# Switched_Outlet_Rev_C.net
KiCad netlist of a schematic drawn in EAGLE
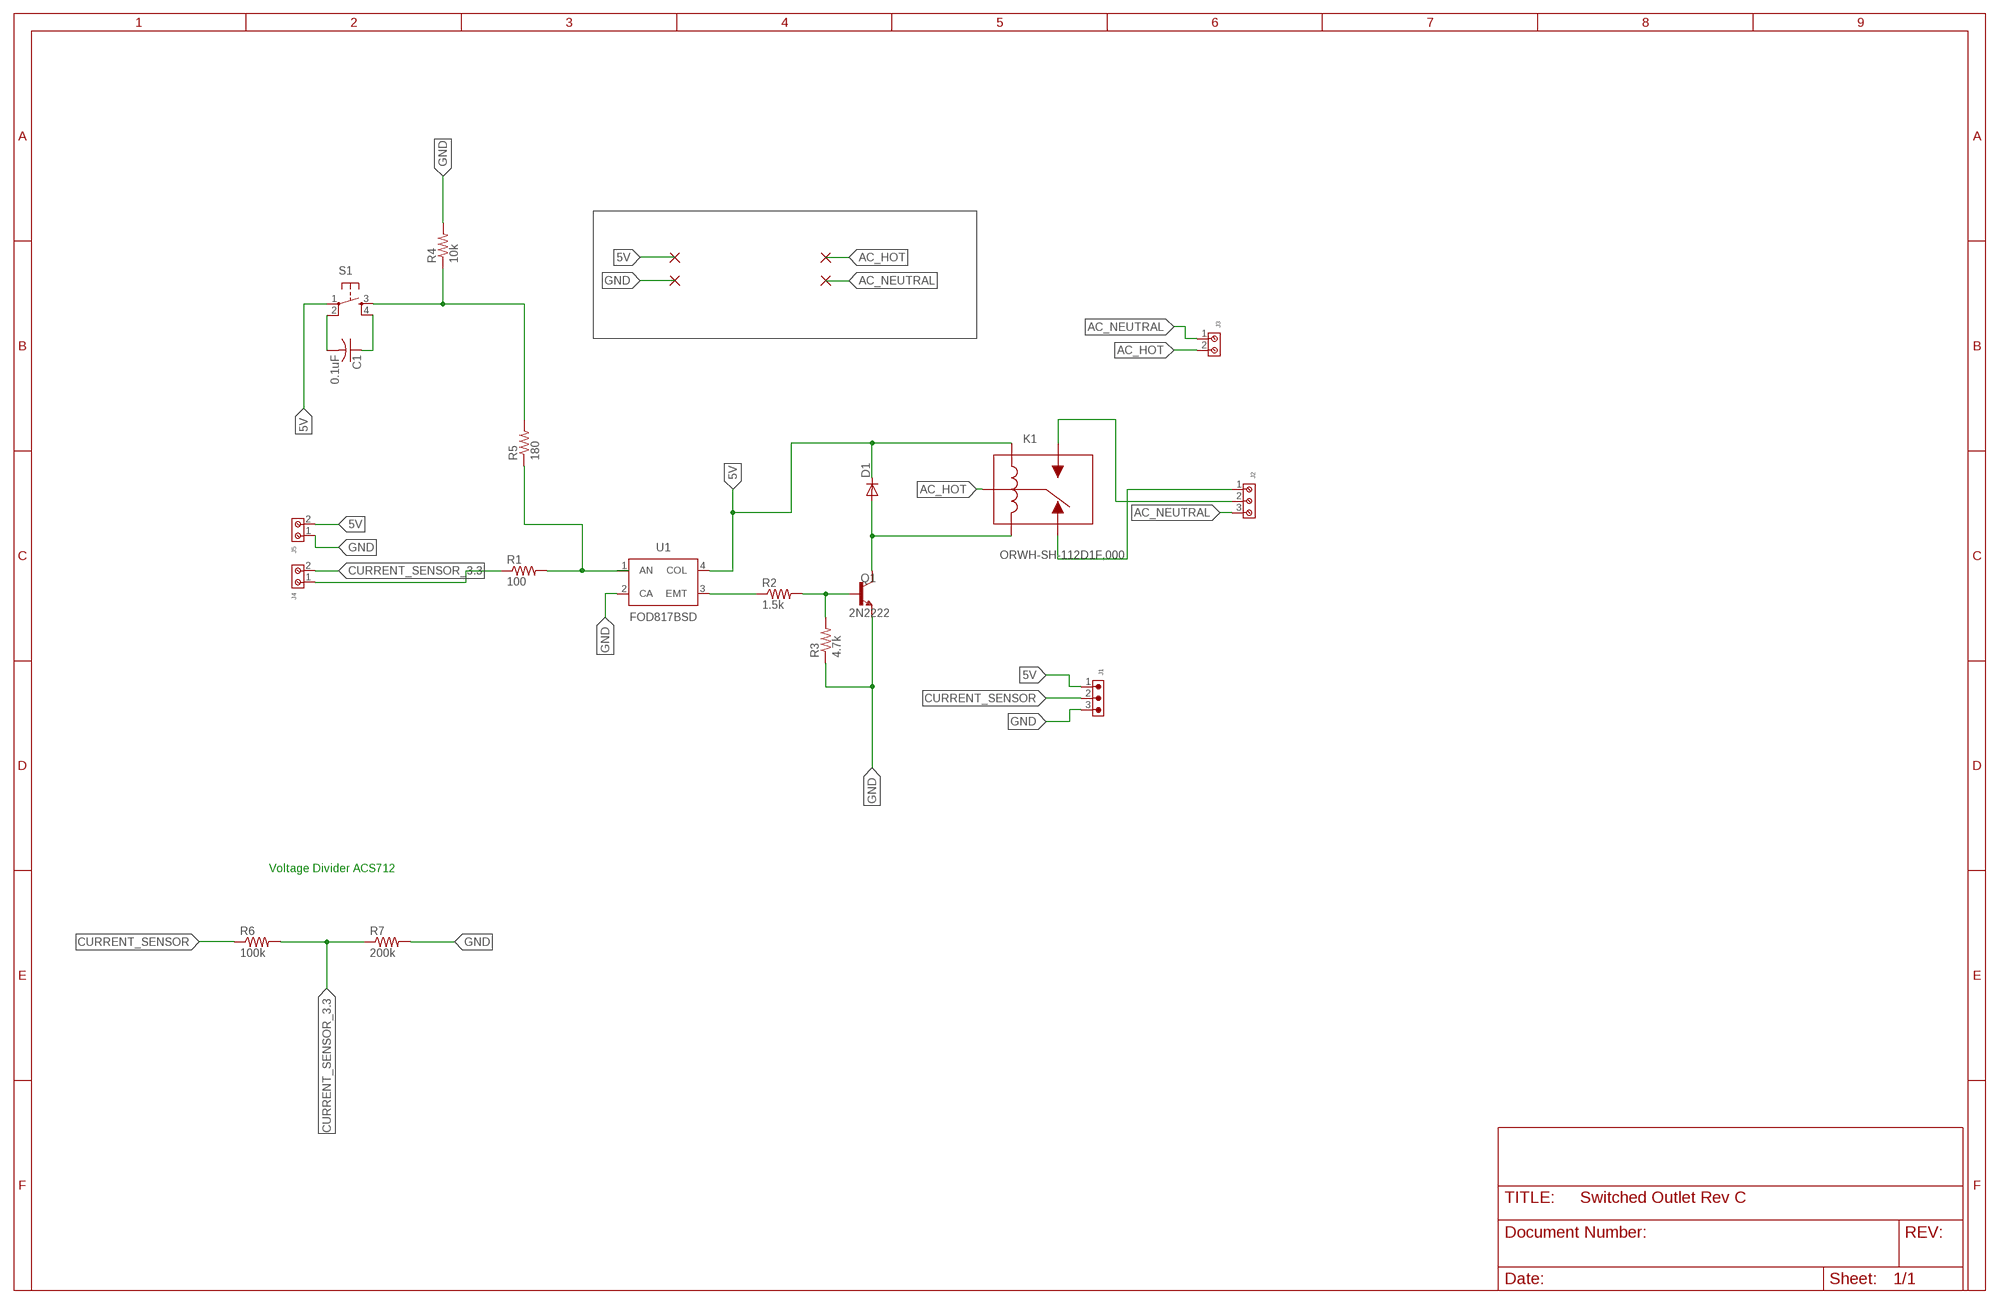
[diagram p0: schematic, sheet 1]

(export (version "E")
  (design (tool "Eeschema 10.0.6"))
  (components
    (comp (ref "C1")
      (value "0.1uF")
      (footprint "eagle-import:C050-024X044")
      (libsource (lib "eagle-import") (part "CAPACITOR-CERAMIC"))
    )
    (comp (ref "D1")
      (value "1N4000")
      (footprint "eagle-import:DO41-10")
      (libsource (lib "eagle-import") (part "1N4000"))
    )
    (comp (ref "J1")
      (value "6130XX11121_61300311121")
      (footprint "eagle-import:61300311121")
      (libsource (lib "eagle-import") (part "6130XX11121_61300311121"))
    )
    (comp (ref "J2")
      (value "691102710003")
      (footprint "eagle-import:691102710003")
      (libsource (lib "eagle-import") (part "691102710003"))
    )
    (comp (ref "J3")
      (value "691102710002")
      (footprint "eagle-import:691102710002")
      (libsource (lib "eagle-import") (part "691102710002"))
    )
    (comp (ref "J4")
      (value "691103110002")
      (footprint "eagle-import:691103110002")
      (libsource (lib "eagle-import") (part "691103110002"))
    )
    (comp (ref "J5")
      (value "691103110002")
      (footprint "eagle-import:691103110002")
      (libsource (lib "eagle-import") (part "691103110002"))
    )
    (comp (ref "K1")
      (value "ORWH-SH-112D1F,000")
      (footprint "eagle-import:ORWH-SH-112D1F,000")
      (fields
        (field (name "DIGIKEY_PART_NUMBER") "PB2029-ND")
        (field (name "MANUFACTURER") "TE Connectivity Potter & Brumfield Relays")
        (field (name "CREATED_BY") "PCBLayout.com")
      )
      (libsource (lib "eagle-import") (part "ORWH-SH-112D1F,000"))
    )
    (comp (ref "Q1")
      (value "2N2222")
      (footprint "eagle-import:TO92-EBC-OVAL")
      (libsource (lib "eagle-import") (part "2N2222"))
    )
    (comp (ref "R1")
      (value "100")
      (footprint "eagle-import:0207_10")
      (libsource (lib "eagle-import") (part "RESISTOR"))
    )
    (comp (ref "R2")
      (value "1.5k")
      (footprint "eagle-import:0207_10")
      (libsource (lib "eagle-import") (part "RESISTOR"))
    )
    (comp (ref "R3")
      (value "4.7k")
      (footprint "eagle-import:0207_10")
      (libsource (lib "eagle-import") (part "RESISTOR"))
    )
    (comp (ref "R4")
      (value "10k")
      (footprint "eagle-import:0207_10")
      (libsource (lib "eagle-import") (part "RESISTOR"))
    )
    (comp (ref "R5")
      (value "180")
      (footprint "eagle-import:0207_10")
      (libsource (lib "eagle-import") (part "RESISTOR"))
    )
    (comp (ref "R6")
      (value "100k")
      (footprint "eagle-import:0207_10")
      (libsource (lib "eagle-import") (part "RESISTOR"))
    )
    (comp (ref "R7")
      (value "200k")
      (footprint "eagle-import:0207_10")
      (libsource (lib "eagle-import") (part "RESISTOR"))
    )
    (comp (ref "S1")
      (value "TACTILE-BUTTON10XX")
      (footprint "eagle-import:B3F-10XX")
      (libsource (lib "eagle-import") (part "TACTILE-BUTTON10XX"))
    )
    (comp (ref "U1")
      (value "FOD817BSD")
      (footprint "eagle-import:DIP1016W60P279L460H460Q4B")
      (fields (field (name "MANUFACTURER") "ON Semiconductor"))
      (libsource (lib "eagle-import") (part "FOD817BSDSMT"))
    )
  )
  (nets
    (net (code "1") (name "5V") (class "Default")
      (node (ref "D1") (pin "C") (pinfunction "C_C") (pintype "passive"))
      (node (ref "J1") (pin "1") (pinfunction "1_1") (pintype "passive"))
      (node (ref "J5") (pin "2") (pinfunction "2_2") (pintype "passive"))
      (node (ref "K1") (pin "1") (pinfunction "1_1") (pintype "passive"))
      (node (ref "S1") (pin "1") (pinfunction "P_1") (pintype "passive"))
      (node (ref "U1") (pin "4") (pinfunction "COL_4") (pintype "input"))
    )
    (net (code "2") (name "AC_HOT") (class "Default")
      (node (ref "J3") (pin "2") (pinfunction "2_2") (pintype "passive"))
      (node (ref "K1") (pin "2") (pinfunction "2_2") (pintype "passive"))
    )
    (net (code "3") (name "AC_NEUTRAL") (class "Default")
      (node (ref "J2") (pin "3") (pinfunction "3_3") (pintype "passive"))
      (node (ref "J3") (pin "1") (pinfunction "1_1") (pintype "passive"))
    )
    (net (code "4") (name "CURRENT_SENSOR") (class "Default")
      (node (ref "J1") (pin "2") (pinfunction "2_2") (pintype "passive"))
      (node (ref "R6") (pin "1") (pinfunction "1_1") (pintype "passive"))
    )
    (net (code "5") (name "CURRENT_SENSOR_3.3") (class "Default")
      (node (ref "J4") (pin "2") (pinfunction "2_2") (pintype "passive"))
      (node (ref "R6") (pin "2") (pinfunction "2_2") (pintype "passive"))
      (node (ref "R7") (pin "1") (pinfunction "1_1") (pintype "passive"))
    )
    (net (code "6") (name "GND") (class "Default")
      (node (ref "J1") (pin "3") (pinfunction "3_3") (pintype "passive"))
      (node (ref "J5") (pin "1") (pinfunction "1_1") (pintype "passive"))
      (node (ref "Q1") (pin "E") (pinfunction "E_E") (pintype "passive"))
      (node (ref "R3") (pin "1") (pinfunction "1_1") (pintype "passive"))
      (node (ref "R4") (pin "2") (pinfunction "2_2") (pintype "passive"))
      (node (ref "R7") (pin "2") (pinfunction "2_2") (pintype "passive"))
      (node (ref "U1") (pin "2") (pinfunction "CA_2") (pintype "bidirectional"))
    )
    (net (code "7") (name "Net-(D1-PadA)") (class "Default")
      (node (ref "D1") (pin "A") (pinfunction "A_A") (pintype "passive"))
      (node (ref "K1") (pin "3") (pinfunction "3_3") (pintype "passive"))
      (node (ref "Q1") (pin "C") (pinfunction "C_C") (pintype "passive"))
    )
    (net (code "8") (name "Net-(J2-Pad1)") (class "Default")
      (node (ref "J2") (pin "1") (pinfunction "1_1") (pintype "passive"))
      (node (ref "K1") (pin "4") (pinfunction "4_4") (pintype "passive"))
    )
    (net (code "9") (name "Net-(J2-Pad2)") (class "Default")
      (node (ref "J2") (pin "2") (pinfunction "2_2") (pintype "passive"))
      (node (ref "K1") (pin "5") (pinfunction "5_5") (pintype "passive"))
    )
    (net (code "10") (name "Net-(J4-Pad1)") (class "Default")
      (node (ref "J4") (pin "1") (pinfunction "1_1") (pintype "passive"))
      (node (ref "R1") (pin "1") (pinfunction "1_1") (pintype "passive"))
    )
    (net (code "11") (name "Net-(Q1-PadB)") (class "Default")
      (node (ref "Q1") (pin "B") (pinfunction "B_B") (pintype "passive"))
      (node (ref "R2") (pin "2") (pinfunction "2_2") (pintype "passive"))
      (node (ref "R3") (pin "2") (pinfunction "2_2") (pintype "passive"))
    )
    (net (code "12") (name "Net-(S1-P1)") (class "Default")
      (node (ref "C1") (pin "2") (pinfunction "2_2") (pintype "passive"))
      (node (ref "S1") (pin "2") (pinfunction "P1_2") (pintype "passive"))
    )
    (net (code "13") (name "Net-(S1-S)") (class "Default")
      (node (ref "R4") (pin "1") (pinfunction "1_1") (pintype "passive"))
      (node (ref "R5") (pin "2") (pinfunction "2_2") (pintype "passive"))
      (node (ref "S1") (pin "3") (pinfunction "S_3") (pintype "passive"))
    )
    (net (code "14") (name "Net-(S1-S1)") (class "Default")
      (node (ref "C1") (pin "1") (pinfunction "1_1") (pintype "passive"))
      (node (ref "S1") (pin "4") (pinfunction "S1_4") (pintype "passive"))
    )
    (net (code "15") (name "Net-(U1-AN)") (class "Default")
      (node (ref "R1") (pin "2") (pinfunction "2_2") (pintype "passive"))
      (node (ref "R5") (pin "1") (pinfunction "1_1") (pintype "passive"))
      (node (ref "U1") (pin "1") (pinfunction "AN_1") (pintype "bidirectional"))
    )
    (net (code "16") (name "Net-(U1-EMT)") (class "Default")
      (node (ref "R2") (pin "1") (pinfunction "1_1") (pintype "passive"))
      (node (ref "U1") (pin "3") (pinfunction "EMT_3") (pintype "output"))
    )
  )
)
